# CAN-Breakout2021_02.net
KiCad netlist of a schematic drawn in EAGLE
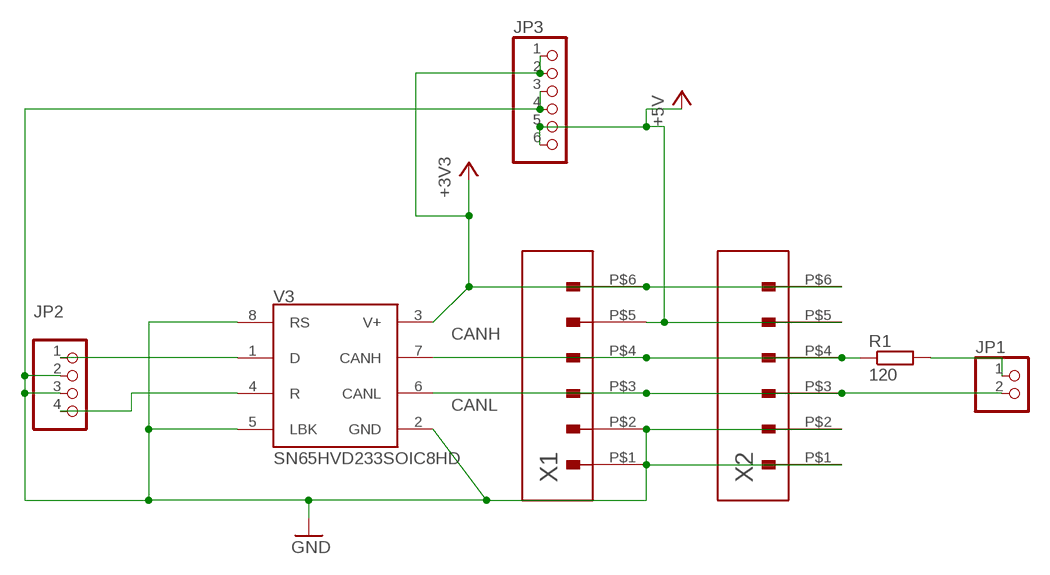
[diagram p0: schematic, sheet 1]

(export (version "E")
  (design (tool "Eeschema 10.0.6"))
  (components
    (comp (ref "JP1")
      (value "PINHD-1X2/90")
      (footprint "eagle-import:1X02_90")
      (libsource (lib "eagle-import") (part "PINHD-1X2/90"))
    )
    (comp (ref "JP2")
      (value "PINHD-1X4")
      (footprint "eagle-import:1X04")
      (libsource (lib "eagle-import") (part "PINHD-1X4"))
    )
    (comp (ref "JP3")
      (value "PINHD-1X6")
      (footprint "eagle-import:1X06")
      (libsource (lib "eagle-import") (part "PINHD-1X6"))
    )
    (comp (ref "R1")
      (value "120")
      (footprint "eagle-import:R0603")
      (libsource (lib "eagle-import") (part "R-EU_R0603"))
    )
    (comp (ref "V3")
      (value "SN65HVD233SOIC8HD")
      (footprint "eagle-import:SO08")
      (libsource (lib "eagle-import") (part "SN65HVD233HDSOIC8"))
    )
    (comp (ref "X1")
      (value "MOLEX104078-0610")
      (footprint "eagle-import:MOLEX104078-0610")
      (libsource (lib "eagle-import") (part "MOLEX104078-0610"))
    )
    (comp (ref "X2")
      (value "MOLEX104078-0610")
      (footprint "eagle-import:MOLEX104078-0610")
      (libsource (lib "eagle-import") (part "MOLEX104078-0610"))
    )
  )
  (nets
    (net (code "1") (name "+3V3") (class "Default")
      (node (ref "JP3") (pin "1") (pinfunction "1_1") (pintype "passive"))
      (node (ref "JP3") (pin "2") (pinfunction "2_2") (pintype "passive"))
      (node (ref "V3") (pin "3") (pinfunction "V+_3") (pintype "power_in"))
      (node (ref "X1") (pin "P$6") (pinfunction "6_P$6") (pintype "passive"))
      (node (ref "X2") (pin "P$6") (pinfunction "6_P$6") (pintype "passive"))
    )
    (net (code "2") (name "+5V") (class "Default")
      (node (ref "JP3") (pin "5") (pinfunction "5_5") (pintype "passive"))
      (node (ref "JP3") (pin "6") (pinfunction "6_6") (pintype "passive"))
      (node (ref "X1") (pin "P$5") (pinfunction "5_P$5") (pintype "passive"))
      (node (ref "X2") (pin "P$5") (pinfunction "5_P$5") (pintype "passive"))
    )
    (net (code "3") (name "/CANH") (class "Default")
      (node (ref "R1") (pin "1") (pinfunction "1_1") (pintype "passive"))
      (node (ref "V3") (pin "7") (pinfunction "CANH_7") (pintype "output"))
      (node (ref "X1") (pin "P$4") (pinfunction "4_P$4") (pintype "passive"))
      (node (ref "X2") (pin "P$4") (pinfunction "4_P$4") (pintype "passive"))
    )
    (net (code "4") (name "/CANL") (class "Default")
      (node (ref "JP1") (pin "2") (pinfunction "2_2") (pintype "passive"))
      (node (ref "V3") (pin "6") (pinfunction "CANL_6") (pintype "output"))
      (node (ref "X1") (pin "P$3") (pinfunction "3_P$3") (pintype "passive"))
      (node (ref "X2") (pin "P$3") (pinfunction "3_P$3") (pintype "passive"))
    )
    (net (code "5") (name "GND") (class "Default")
      (node (ref "JP2") (pin "2") (pinfunction "2_2") (pintype "passive"))
      (node (ref "JP2") (pin "3") (pinfunction "3_3") (pintype "passive"))
      (node (ref "JP3") (pin "3") (pinfunction "3_3") (pintype "passive"))
      (node (ref "JP3") (pin "4") (pinfunction "4_4") (pintype "passive"))
      (node (ref "V3") (pin "2") (pinfunction "GND_2") (pintype "power_in"))
      (node (ref "V3") (pin "5") (pinfunction "LBK_5") (pintype "input"))
      (node (ref "V3") (pin "8") (pinfunction "RS_8") (pintype "input"))
      (node (ref "X1") (pin "P$1") (pinfunction "1_P$1") (pintype "passive"))
      (node (ref "X1") (pin "P$2") (pinfunction "2_P$2") (pintype "passive"))
      (node (ref "X2") (pin "P$1") (pinfunction "1_P$1") (pintype "passive"))
      (node (ref "X2") (pin "P$2") (pinfunction "2_P$2") (pintype "passive"))
    )
    (net (code "6") (name "Net-(JP1-Pad1)") (class "Default")
      (node (ref "JP1") (pin "1") (pinfunction "1_1") (pintype "passive"))
      (node (ref "R1") (pin "2") (pinfunction "2_2") (pintype "passive"))
    )
    (net (code "7") (name "Net-(V3-D)") (class "Default")
      (node (ref "JP2") (pin "1") (pinfunction "1_1") (pintype "passive"))
      (node (ref "V3") (pin "1") (pinfunction "D_1") (pintype "input"))
    )
    (net (code "8") (name "Net-(V3-R)") (class "Default")
      (node (ref "JP2") (pin "4") (pinfunction "4_4") (pintype "passive"))
      (node (ref "V3") (pin "4") (pinfunction "R_4") (pintype "input"))
    )
  )
)
